# USB_OTG_HS.net
KiCad netlist of a schematic drawn in Altium Designer
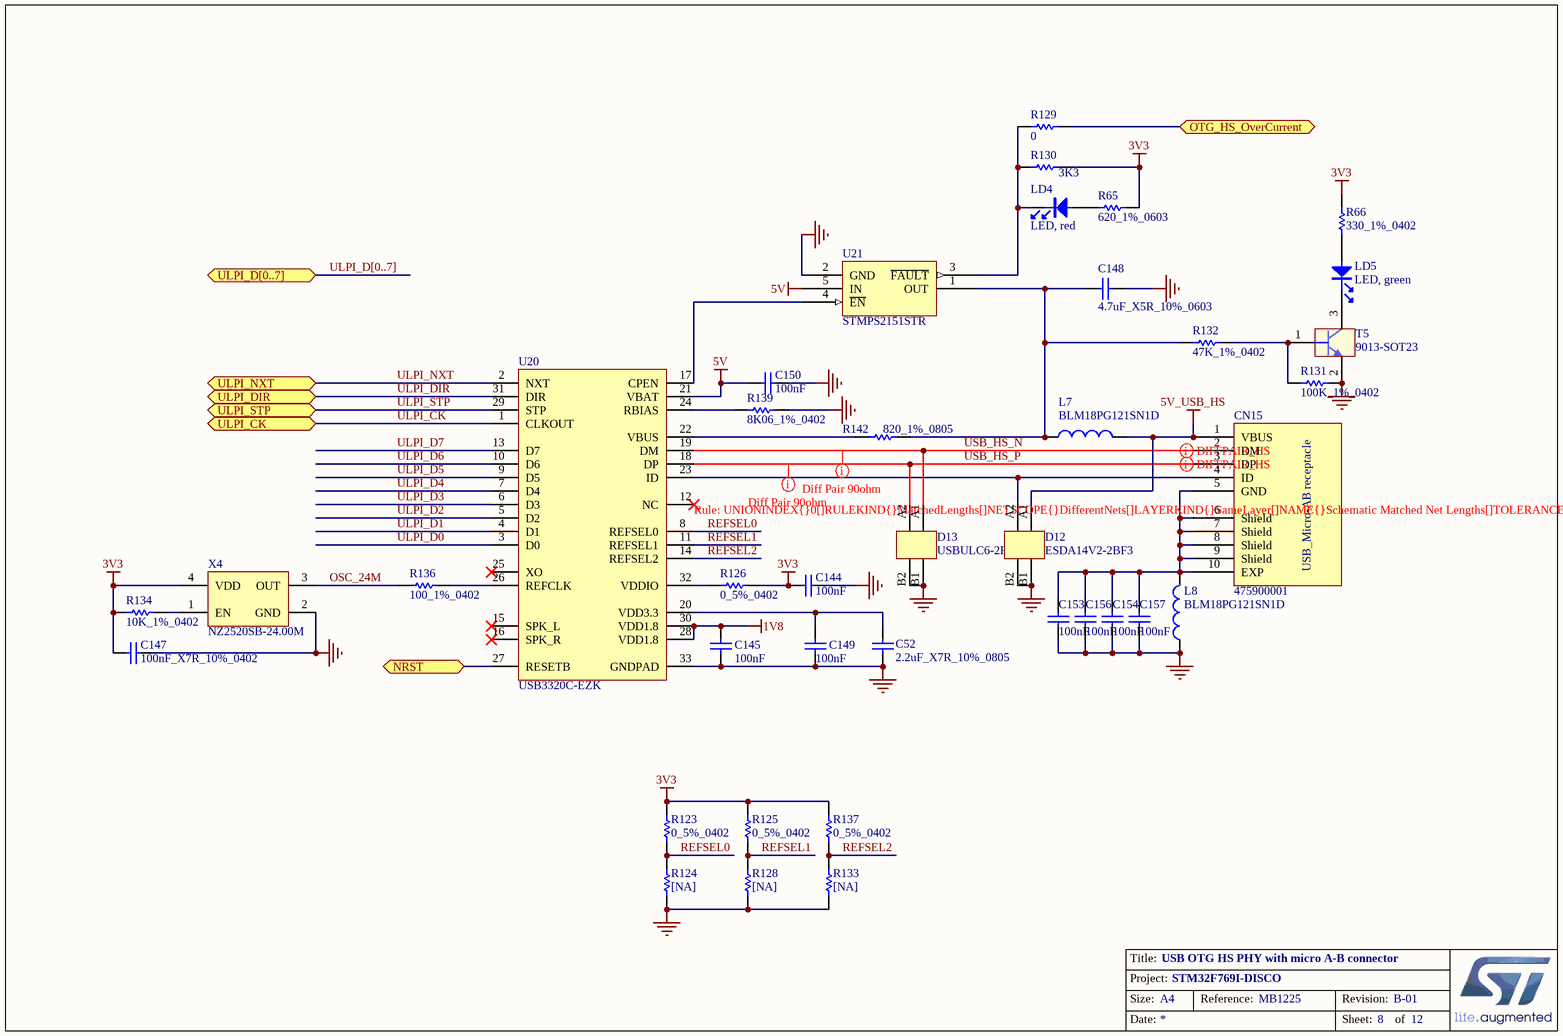
[diagram p0: USB_OTG_HS.SchDoc]

(export (version "E")
  (design (tool "Eeschema 10.0.6"))
  (components
    (comp (ref "C52")
      (value "2.2uF_X7R_10%_0805")
      (footprint "TAN-A")
      (description "Capacitor,2.2uF,16V, X7R,10%,0805,YAGEO")
      (libsource (lib "MCD_TOOLS") (part "Cap_2.2uF_X7R_10%_0805"))
    )
    (comp (ref "C144")
      (value "100nF")
      (footprint "0402C")
      (description "Capacitor,100nF,16V,X7R,10%,0402,YAGEO")
      (libsource (lib "MCD_TOOLS") (part "Cap_100nF_X7R_10%_0402"))
    )
    (comp (ref "C145")
      (value "100nF")
      (footprint "0402C")
      (description "Capacitor,100nF,16V,X7R,10%,0402,YAGEO")
      (libsource (lib "MCD_TOOLS") (part "Cap_100nF_X7R_10%_0402"))
    )
    (comp (ref "C147")
      (value "100nF_X7R_10%_0402")
      (footprint "0402C")
      (description "Capacitor,100nF,16V,X7R,10%,0402,YAGEO")
      (libsource (lib "MCD_TOOLS_CAPACITOR") (part "Cap_100nF_X7R_10%_0402"))
    )
    (comp (ref "C148")
      (value "4.7uF_X5R_10%_0603")
      (footprint "0603C")
      (description "Capacitor,4.7uF,16V, X5R,10%,0603,YAGEO")
      (libsource (lib "MCD_TOOLS") (part "Cap_4.7uF_X5R_10%_0603"))
    )
    (comp (ref "C149")
      (value "100nF")
      (footprint "0402C")
      (description "Capacitor,100nF,16V,X7R,10%,0402,YAGEO")
      (libsource (lib "MCD_TOOLS") (part "Cap_100nF_X7R_10%_0402"))
    )
    (comp (ref "C150")
      (value "100nF")
      (footprint "0402C")
      (description "Capacitor,100nF,16V,X7R,10%,0402,YAGEO")
      (libsource (lib "MCD_TOOLS") (part "Cap_100nF_X7R_10%_0402"))
    )
    (comp (ref "C153")
      (value "100nF")
      (footprint "0402C")
      (description "Capacitor,100nF,16V,X7R,10%,0402,YAGEO")
      (libsource (lib "MCD_TOOLS") (part "Cap_100nF_X7R_10%_0402"))
    )
    (comp (ref "C154")
      (value "100nF")
      (footprint "0402C")
      (description "Capacitor,100nF,16V,X7R,10%,0402,YAGEO")
      (libsource (lib "MCD_TOOLS") (part "Cap_100nF_X7R_10%_0402"))
    )
    (comp (ref "C156")
      (value "100nF")
      (footprint "0402C")
      (description "Capacitor,100nF,16V,X7R,10%,0402,YAGEO")
      (libsource (lib "MCD_TOOLS") (part "Cap_100nF_X7R_10%_0402"))
    )
    (comp (ref "C157")
      (value "100nF")
      (footprint "0402C")
      (description "Capacitor,100nF,16V,X7R,10%,0402,YAGEO")
      (libsource (lib "MCD_TOOLS") (part "Cap_100nF_X7R_10%_0402"))
    )
    (comp (ref "CN15")
      (value "475900001")
      (footprint "MOLEX_47590001")
      (description "USB-MICRO-AB, 47590-0001, SMT, MOLEX")
      (libsource (lib "MCD_TOOLS") (part "475900001"))
    )
    (comp (ref "D12")
      (value "ESDA14V2-2BF3")
      (footprint "BGA4_0R4_0R8X0R8")
      (description "Quad bidirectional Transil array for ESD protection")
      (libsource (lib "MCD_TOOLS_MISCELLANEOUS") (part "ESDA14V2-2BF3"))
    )
    (comp (ref "D13")
      (value "USBULC6-2F3")
      (footprint "BGA4_0R4_0R8X0R8")
      (description "2-line Transil, (TVS), ultralow capacitance protection for high speed USB")
      (libsource (lib "MCD_TOOLS_MISCELLANEOUS") (part "USBULC6-2F3"))
    )
    (comp (ref "L7")
      (value "BLM18PG121SN1D")
      (footprint "0603L")
      (description "Bead,120R,2A,0603,BLM18PG121SN1D,MURATA")
      (libsource (lib "MCD_TOOLS") (part "BEAD_120R_2A_0603"))
    )
    (comp (ref "L8")
      (value "BLM18PG121SN1D")
      (footprint "0603L")
      (description "Bead,120R,2A,0603,BLM18PG121SN1D,MURATA")
      (libsource (lib "MCD_TOOLS") (part "BEAD_120R_2A_0603"))
    )
    (comp (ref "LD4")
      (value "LED, red")
      (footprint "0603D")
      (description "LED,red,0603,19-213-R6C-AP1Q2B/3T,everlight")
      (libsource (lib "MCD_TOOLS") (part "LED_red"))
    )
    (comp (ref "LD5")
      (value "LED, green")
      (footprint "0603D")
      (description "LED,green,0603,19-213SYGC/S530-E2/TR8,everlight")
      (libsource (lib "MCD_TOOLS") (part "LED_green"))
    )
    (comp (ref "R65")
      (value "620_1%_0603")
      (footprint "0603R")
      (description "Resistor,620,0603,1%,VISHAY")
      (libsource (lib "MCD_TOOLS") (part "Res_620_1%_0603"))
    )
    (comp (ref "R66")
      (value "330_1%_0402")
      (footprint "0402R")
      (description "Resistor,330,0402,1%,YAGEO")
      (libsource (lib "MCD_TOOLS") (part "Res_330_1%_0402"))
    )
    (comp (ref "R123")
      (value "0_5%_0402")
      (footprint "0402R")
      (description "Resistor,0,0402,5%,YAGEO")
      (libsource (lib "MCD_TOOLS") (part "Res_0_5%_0402"))
    )
    (comp (ref "R124")
      (value "[NA]")
      (footprint "0402R")
      (description "Resistor,[NA],0402")
      (libsource (lib "MCD_TOOLS") (part "Res_NA_0402"))
    )
    (comp (ref "R125")
      (value "0_5%_0402")
      (footprint "0402R")
      (description "Resistor,0,0402,5%,YAGEO")
      (libsource (lib "MCD_TOOLS") (part "Res_0_5%_0402"))
    )
    (comp (ref "R126")
      (value "0_5%_0402")
      (footprint "0402R")
      (description "Resistor,0,0402,5%,YAGEO")
      (libsource (lib "MCD_TOOLS") (part "Res_0_5%_0402"))
    )
    (comp (ref "R128")
      (value "[NA]")
      (footprint "0402R")
      (description "Resistor,[NA],0402")
      (libsource (lib "MCD_TOOLS") (part "Res_NA_0402"))
    )
    (comp (ref "R129")
      (value "0")
      (footprint "0402R")
      (description "Resistor,0,0402,5%,YAGEO")
      (libsource (lib "MCD_TOOLS") (part "Res_0_5%_0402"))
    )
    (comp (ref "R130")
      (value "3K3")
      (footprint "0402R")
      (description "Resistor,3K3,0402,1%,YAGEO")
      (libsource (lib "MCD_TOOLS") (part "Res_3K3_1%_0402"))
    )
    (comp (ref "R131")
      (value "100K_1%_0402")
      (footprint "0402R")
      (description "Resistor,100K,0402,1%,YAGEO")
      (libsource (lib "MCD_TOOLS_RESISTOR") (part "Res_100K_1%_0402"))
    )
    (comp (ref "R132")
      (value "47K_1%_0402")
      (footprint "0402R")
      (description "Resistor,47K,0402,1%,YAGEO")
      (libsource (lib "MCD_TOOLS") (part "Res_47K_1%_0402"))
    )
    (comp (ref "R133")
      (value "[NA]")
      (footprint "0402R")
      (description "Resistor,[NA],0402")
      (libsource (lib "MCD_TOOLS") (part "Res_NA_0402"))
    )
    (comp (ref "R134")
      (value "10K_1%_0402")
      (footprint "0402R")
      (description "Resistor,10K,0402,1%,YAGEO")
      (libsource (lib "MCD_TOOLS") (part "Res_10K_1%_0402"))
    )
    (comp (ref "R136")
      (value "100_1%_0402")
      (footprint "0402R")
      (description "Resistor,100,0402,1%,YAGEO")
      (libsource (lib "MCD_TOOLS") (part "Res_100_1%_0402"))
    )
    (comp (ref "R137")
      (value "0_5%_0402")
      (footprint "0402R")
      (description "Resistor,0,0402,5%,YAGEO")
      (libsource (lib "MCD_TOOLS") (part "Res_0_5%_0402"))
    )
    (comp (ref "R139")
      (value "8K06_1%_0402")
      (footprint "0402R")
      (description "Resistor,8K06,0402,1%,YAGEO")
      (libsource (lib "MCD_TOOLS") (part "Res_8K06_1%_0402"))
    )
    (comp (ref "R142")
      (value "820_1%_0805")
      (footprint "0805R")
      (description "Resistor,820,0805,1%,YAGEO")
      (libsource (lib "MCD_TOOLS") (part "Res_820_1%_0805"))
    )
    (comp (ref "T5")
      (value "9013-SOT23")
      (footprint "SOT-23")
      (description "NPN Bipolar Transistor, SOT-23 Footprint")
      (libsource (lib "MCD_TOOLS_MISCELLANEOUS") (part "9013-SOT23"))
    )
    (comp (ref "U20")
      (value "USB3320C-EZK")
      (footprint "QFN32_0R5_5X5")
      (description "USB3320C, Hi-Speed USB Host, Device or OTG PHY with ULPI Low Pin Interface")
      (fields (field (name "PROVIDED") "Sub Co"))
      (libsource (lib "MCD_TOOLS_MISCELLANEOUS") (part "USB3320C-EZK"))
    )
    (comp (ref "U21")
      (value "STMPS2151STR")
      (footprint "SOT23-5")
      (description "Enhanced single channel power switches")
      (libsource (lib "MCD_TOOLS_MISCELLANEOUS") (part "STMPS2151STR"))
    )
    (comp (ref "X4")
      (value "NZ2520SB-24.00M")
      (footprint "OSC_4SM_2R5X2")
      (description "Oscillator 24.00Mhz, -+50PPM, 3.3V, Temp -55 to +125°C")
      (libsource (lib "MCD_TOOLS_MISCELLANEOUS") (part "OSC_24M_NZ2520SB"))
    )
  )
  (nets
    (net (code "1") (name "/NRST") (class "Default")
      (node (ref "U20") (pin "27") (pinfunction "RESETB_27") (pintype "passive"))
    )
    (net (code "2") (name "/OSC_24M") (class "Default")
      (node (ref "R136") (pin "1") (pinfunction "1_1") (pintype "passive"))
      (node (ref "X4") (pin "3") (pinfunction "OUT_3") (pintype "passive"))
    )
    (net (code "3") (name "/OTG_HS_OverCurrent") (class "Default")
      (node (ref "R129") (pin "2") (pinfunction "2_2") (pintype "passive"))
    )
    (net (code "4") (name "/REFSEL0") (class "Default")
      (node (ref "R123") (pin "1") (pinfunction "1_1") (pintype "passive"))
      (node (ref "R124") (pin "2") (pinfunction "2_2") (pintype "passive"))
      (node (ref "U20") (pin "8") (pinfunction "REFSEL0_8") (pintype "passive"))
    )
    (net (code "5") (name "/REFSEL1") (class "Default")
      (node (ref "R125") (pin "1") (pinfunction "1_1") (pintype "passive"))
      (node (ref "R128") (pin "2") (pinfunction "2_2") (pintype "passive"))
      (node (ref "U20") (pin "11") (pinfunction "REFSEL1_11") (pintype "passive"))
    )
    (net (code "6") (name "/REFSEL2") (class "Default")
      (node (ref "R133") (pin "2") (pinfunction "2_2") (pintype "passive"))
      (node (ref "R137") (pin "1") (pinfunction "1_1") (pintype "passive"))
      (node (ref "U20") (pin "14") (pinfunction "REFSEL2_14") (pintype "passive"))
    )
    (net (code "7") (name "/ULPI_CK") (class "Default")
      (node (ref "U20") (pin "1") (pinfunction "CLKOUT_1") (pintype "passive"))
    )
    (net (code "8") (name "/ULPI_D0") (class "Default")
      (node (ref "U20") (pin "3") (pinfunction "D0_3") (pintype "passive"))
    )
    (net (code "9") (name "/ULPI_D1") (class "Default")
      (node (ref "U20") (pin "4") (pinfunction "D1_4") (pintype "passive"))
    )
    (net (code "10") (name "/ULPI_D2") (class "Default")
      (node (ref "U20") (pin "5") (pinfunction "D2_5") (pintype "passive"))
    )
    (net (code "11") (name "/ULPI_D3") (class "Default")
      (node (ref "U20") (pin "6") (pinfunction "D3_6") (pintype "passive"))
    )
    (net (code "12") (name "/ULPI_D4") (class "Default")
      (node (ref "U20") (pin "7") (pinfunction "D4_7") (pintype "passive"))
    )
    (net (code "13") (name "/ULPI_D5") (class "Default")
      (node (ref "U20") (pin "9") (pinfunction "D5_9") (pintype "passive"))
    )
    (net (code "14") (name "/ULPI_D6") (class "Default")
      (node (ref "U20") (pin "10") (pinfunction "D6_10") (pintype "passive"))
    )
    (net (code "15") (name "/ULPI_D7") (class "Default")
      (node (ref "U20") (pin "13") (pinfunction "D7_13") (pintype "passive"))
    )
    (net (code "16") (name "/ULPI_DIR") (class "Default")
      (node (ref "U20") (pin "31") (pinfunction "DIR_31") (pintype "passive"))
    )
    (net (code "18") (name "/ULPI_NXT") (class "Default")
      (node (ref "U20") (pin "2") (pinfunction "NXT_2") (pintype "passive"))
    )
    (net (code "19") (name "/ULPI_STP") (class "Default")
      (node (ref "U20") (pin "29") (pinfunction "STP_29") (pintype "passive"))
    )
    (net (code "20") (name "/USB_HS_N") (class "Default")
      (node (ref "CN15") (pin "2") (pinfunction "DM_2") (pintype "passive"))
      (node (ref "D13") (pin "A1") (pintype "passive"))
      (node (ref "U20") (pin "19") (pinfunction "DM_19") (pintype "passive"))
    )
    (net (code "21") (name "/USB_HS_P") (class "Default")
      (node (ref "CN15") (pin "3") (pinfunction "DP_3") (pintype "passive"))
      (node (ref "D13") (pin "A2") (pintype "passive"))
      (node (ref "U20") (pin "18") (pinfunction "DP_18") (pintype "passive"))
    )
    (net (code "22") (name "1V8") (class "Default")
      (node (ref "C145") (pin "2") (pinfunction "2_2") (pintype "passive"))
      (node (ref "U20") (pin "28") (pinfunction "VDD1.8_28") (pintype "passive"))
      (node (ref "U20") (pin "30") (pinfunction "VDD1.8_30") (pintype "passive"))
    )
    (net (code "23") (name "3V3") (class "Default")
      (node (ref "C144") (pin "1") (pinfunction "1_1") (pintype "passive"))
      (node (ref "C147") (pin "1") (pinfunction "1_1") (pintype "passive"))
      (node (ref "R123") (pin "2") (pinfunction "2_2") (pintype "passive"))
      (node (ref "R125") (pin "2") (pinfunction "2_2") (pintype "passive"))
      (node (ref "R126") (pin "2") (pinfunction "2_2") (pintype "passive"))
      (node (ref "R130") (pin "1") (pinfunction "1_1") (pintype "passive"))
      (node (ref "R134") (pin "1") (pinfunction "1_1") (pintype "passive"))
      (node (ref "R137") (pin "2") (pinfunction "2_2") (pintype "passive"))
      (node (ref "R65") (pin "2") (pinfunction "2_2") (pintype "passive"))
      (node (ref "R66") (pin "2") (pinfunction "2_2") (pintype "passive"))
      (node (ref "X4") (pin "4") (pinfunction "VDD_4") (pintype "passive"))
    )
    (net (code "24") (name "5V") (class "Default")
      (node (ref "C150") (pin "1") (pinfunction "1_1") (pintype "passive"))
      (node (ref "U20") (pin "21") (pinfunction "VBAT_21") (pintype "passive"))
      (node (ref "U21") (pin "5") (pinfunction "IN_5") (pintype "passive"))
    )
    (net (code "25") (name "5V_USB_HS") (class "Default")
      (node (ref "CN15") (pin "1") (pinfunction "VBUS_1") (pintype "passive"))
      (node (ref "D12") (pin "A1") (pintype "passive"))
      (node (ref "L7") (pin "2") (pinfunction "2_2") (pintype "passive"))
    )
    (net (code "26") (name "GND") (class "Default")
      (node (ref "C144") (pin "2") (pinfunction "2_2") (pintype "passive"))
      (node (ref "C145") (pin "1") (pinfunction "1_1") (pintype "passive"))
      (node (ref "C147") (pin "2") (pinfunction "2_2") (pintype "passive"))
      (node (ref "C148") (pin "2") (pinfunction "2_2") (pintype "passive"))
      (node (ref "C149") (pin "1") (pinfunction "1_1") (pintype "passive"))
      (node (ref "C150") (pin "2") (pinfunction "2_2") (pintype "passive"))
      (node (ref "C153") (pin "1") (pinfunction "1_1") (pintype "passive"))
      (node (ref "C154") (pin "1") (pinfunction "1_1") (pintype "passive"))
      (node (ref "C156") (pin "1") (pinfunction "1_1") (pintype "passive"))
      (node (ref "C157") (pin "1") (pinfunction "1_1") (pintype "passive"))
      (node (ref "C52") (pin "1") (pinfunction "1_1") (pintype "passive"))
      (node (ref "D12") (pin "B1") (pintype "passive"))
      (node (ref "D12") (pin "B2") (pintype "passive"))
      (node (ref "D13") (pin "B1") (pintype "passive"))
      (node (ref "D13") (pin "B2") (pintype "passive"))
      (node (ref "L8") (pin "1") (pinfunction "1_1") (pintype "passive"))
      (node (ref "R124") (pin "1") (pinfunction "1_1") (pintype "passive"))
      (node (ref "R128") (pin "1") (pinfunction "1_1") (pintype "passive"))
      (node (ref "R131") (pin "2") (pinfunction "2_2") (pintype "passive"))
      (node (ref "R133") (pin "1") (pinfunction "1_1") (pintype "passive"))
      (node (ref "R139") (pin "2") (pinfunction "2_2") (pintype "passive"))
      (node (ref "T5") (pin "2") (pinfunction "E_2") (pintype "passive"))
      (node (ref "U20") (pin "33") (pinfunction "GNDPAD_33") (pintype "passive"))
      (node (ref "U21") (pin "2") (pinfunction "GND_2") (pintype "passive"))
      (node (ref "X4") (pin "2") (pinfunction "GND_2") (pintype "passive"))
    )
    (net (code "27") (name "Net-(CN15-EXP)") (class "Default")
      (node (ref "C153") (pin "2") (pinfunction "2_2") (pintype "passive"))
      (node (ref "C154") (pin "2") (pinfunction "2_2") (pintype "passive"))
      (node (ref "C156") (pin "2") (pinfunction "2_2") (pintype "passive"))
      (node (ref "C157") (pin "2") (pinfunction "2_2") (pintype "passive"))
      (node (ref "CN15") (pin "10") (pinfunction "EXP_10") (pintype "passive"))
      (node (ref "CN15") (pin "5") (pinfunction "GND_5") (pintype "passive"))
      (node (ref "CN15") (pin "6") (pinfunction "Shield_6") (pintype "passive"))
      (node (ref "CN15") (pin "7") (pinfunction "Shield_7") (pintype "passive"))
      (node (ref "CN15") (pin "8") (pinfunction "Shield_8") (pintype "passive"))
      (node (ref "CN15") (pin "9") (pinfunction "Shield_9") (pintype "passive"))
      (node (ref "L8") (pin "2") (pinfunction "2_2") (pintype "passive"))
    )
    (net (code "28") (name "Net-(CN15-ID)") (class "Default")
      (node (ref "CN15") (pin "4") (pinfunction "ID_4") (pintype "passive"))
      (node (ref "D12") (pin "A2") (pintype "passive"))
      (node (ref "U20") (pin "23") (pinfunction "ID_23") (pintype "passive"))
    )
    (net (code "29") (name "Net-(LD4-Pad1)") (class "Default")
      (node (ref "LD4") (pin "1") (pintype "passive"))
      (node (ref "R65") (pin "1") (pinfunction "1_1") (pintype "passive"))
    )
    (net (code "30") (name "Net-(LD5-Pad1)") (class "Default")
      (node (ref "LD5") (pin "1") (pintype "passive"))
      (node (ref "R66") (pin "1") (pinfunction "1_1") (pintype "passive"))
    )
    (net (code "31") (name "Net-(T5-B)") (class "Default")
      (node (ref "R131") (pin "1") (pinfunction "1_1") (pintype "passive"))
      (node (ref "R132") (pin "2") (pinfunction "2_2") (pintype "passive"))
      (node (ref "T5") (pin "1") (pinfunction "B_1") (pintype "passive"))
    )
    (net (code "32") (name "Net-(T5-C)") (class "Default")
      (node (ref "LD5") (pin "2") (pintype "passive"))
      (node (ref "T5") (pin "3") (pinfunction "C_3") (pintype "passive"))
    )
    (net (code "33") (name "Net-(U20-CPEN)") (class "Default")
      (node (ref "U20") (pin "17") (pinfunction "CPEN_17") (pintype "passive"))
      (node (ref "U21") (pin "4") (pinfunction "~{EN}_4") (pintype "input"))
    )
    (net (code "34") (name "Net-(U20-RBIAS)") (class "Default")
      (node (ref "R139") (pin "1") (pinfunction "1_1") (pintype "passive"))
      (node (ref "U20") (pin "24") (pinfunction "RBIAS_24") (pintype "passive"))
    )
    (net (code "35") (name "Net-(U20-REFCLK)") (class "Default")
      (node (ref "R136") (pin "2") (pinfunction "2_2") (pintype "passive"))
      (node (ref "U20") (pin "26") (pinfunction "REFCLK_26") (pintype "passive"))
    )
    (net (code "36") (name "Net-(U20-VBUS)") (class "Default")
      (node (ref "R142") (pin "1") (pinfunction "1_1") (pintype "passive"))
      (node (ref "U20") (pin "22") (pinfunction "VBUS_22") (pintype "passive"))
    )
    (net (code "37") (name "Net-(U20-VDD3.3)") (class "Default")
      (node (ref "C149") (pin "2") (pinfunction "2_2") (pintype "passive"))
      (node (ref "C52") (pin "2") (pinfunction "2_2") (pintype "passive"))
      (node (ref "U20") (pin "20") (pinfunction "VDD3.3_20") (pintype "passive"))
    )
    (net (code "38") (name "Net-(U20-VDDIO)") (class "Default")
      (node (ref "R126") (pin "1") (pinfunction "1_1") (pintype "passive"))
      (node (ref "U20") (pin "32") (pinfunction "VDDIO_32") (pintype "passive"))
    )
    (net (code "39") (name "Net-(U21-OUT)") (class "Default")
      (node (ref "C148") (pin "1") (pinfunction "1_1") (pintype "passive"))
      (node (ref "L7") (pin "1") (pinfunction "1_1") (pintype "passive"))
      (node (ref "R132") (pin "1") (pinfunction "1_1") (pintype "passive"))
      (node (ref "R142") (pin "2") (pinfunction "2_2") (pintype "passive"))
      (node (ref "U21") (pin "1") (pinfunction "OUT_1") (pintype "passive"))
    )
    (net (code "40") (name "Net-(U21-~{FAULT})") (class "Default")
      (node (ref "LD4") (pin "2") (pintype "passive"))
      (node (ref "R129") (pin "1") (pinfunction "1_1") (pintype "passive"))
      (node (ref "R130") (pin "2") (pinfunction "2_2") (pintype "passive"))
      (node (ref "U21") (pin "3") (pinfunction "~{FAULT}_3") (pintype "output"))
    )
    (net (code "41") (name "Net-(X4-EN)") (class "Default")
      (node (ref "R134") (pin "2") (pinfunction "2_2") (pintype "passive"))
      (node (ref "X4") (pin "1") (pinfunction "EN_1") (pintype "passive"))
    )
    (net (code "42") (name "unconnected-(U20-NC-Pad12)") (class "Default")
      (node (ref "U20") (pin "12") (pinfunction "NC_12") (pintype "passive+no_connect"))
    )
    (net (code "43") (name "unconnected-(U20-SPK_L-Pad15)") (class "Default")
      (node (ref "U20") (pin "15") (pinfunction "SPK_L_15") (pintype "passive+no_connect"))
    )
    (net (code "44") (name "unconnected-(U20-SPK_R-Pad16)") (class "Default")
      (node (ref "U20") (pin "16") (pinfunction "SPK_R_16") (pintype "passive+no_connect"))
    )
    (net (code "45") (name "unconnected-(U20-XO-Pad25)") (class "Default")
      (node (ref "U20") (pin "25") (pinfunction "XO_25") (pintype "passive+no_connect"))
    )
  )
)
